# Jukebox_Processing.net
KiCad netlist of a schematic drawn in Altium Designer
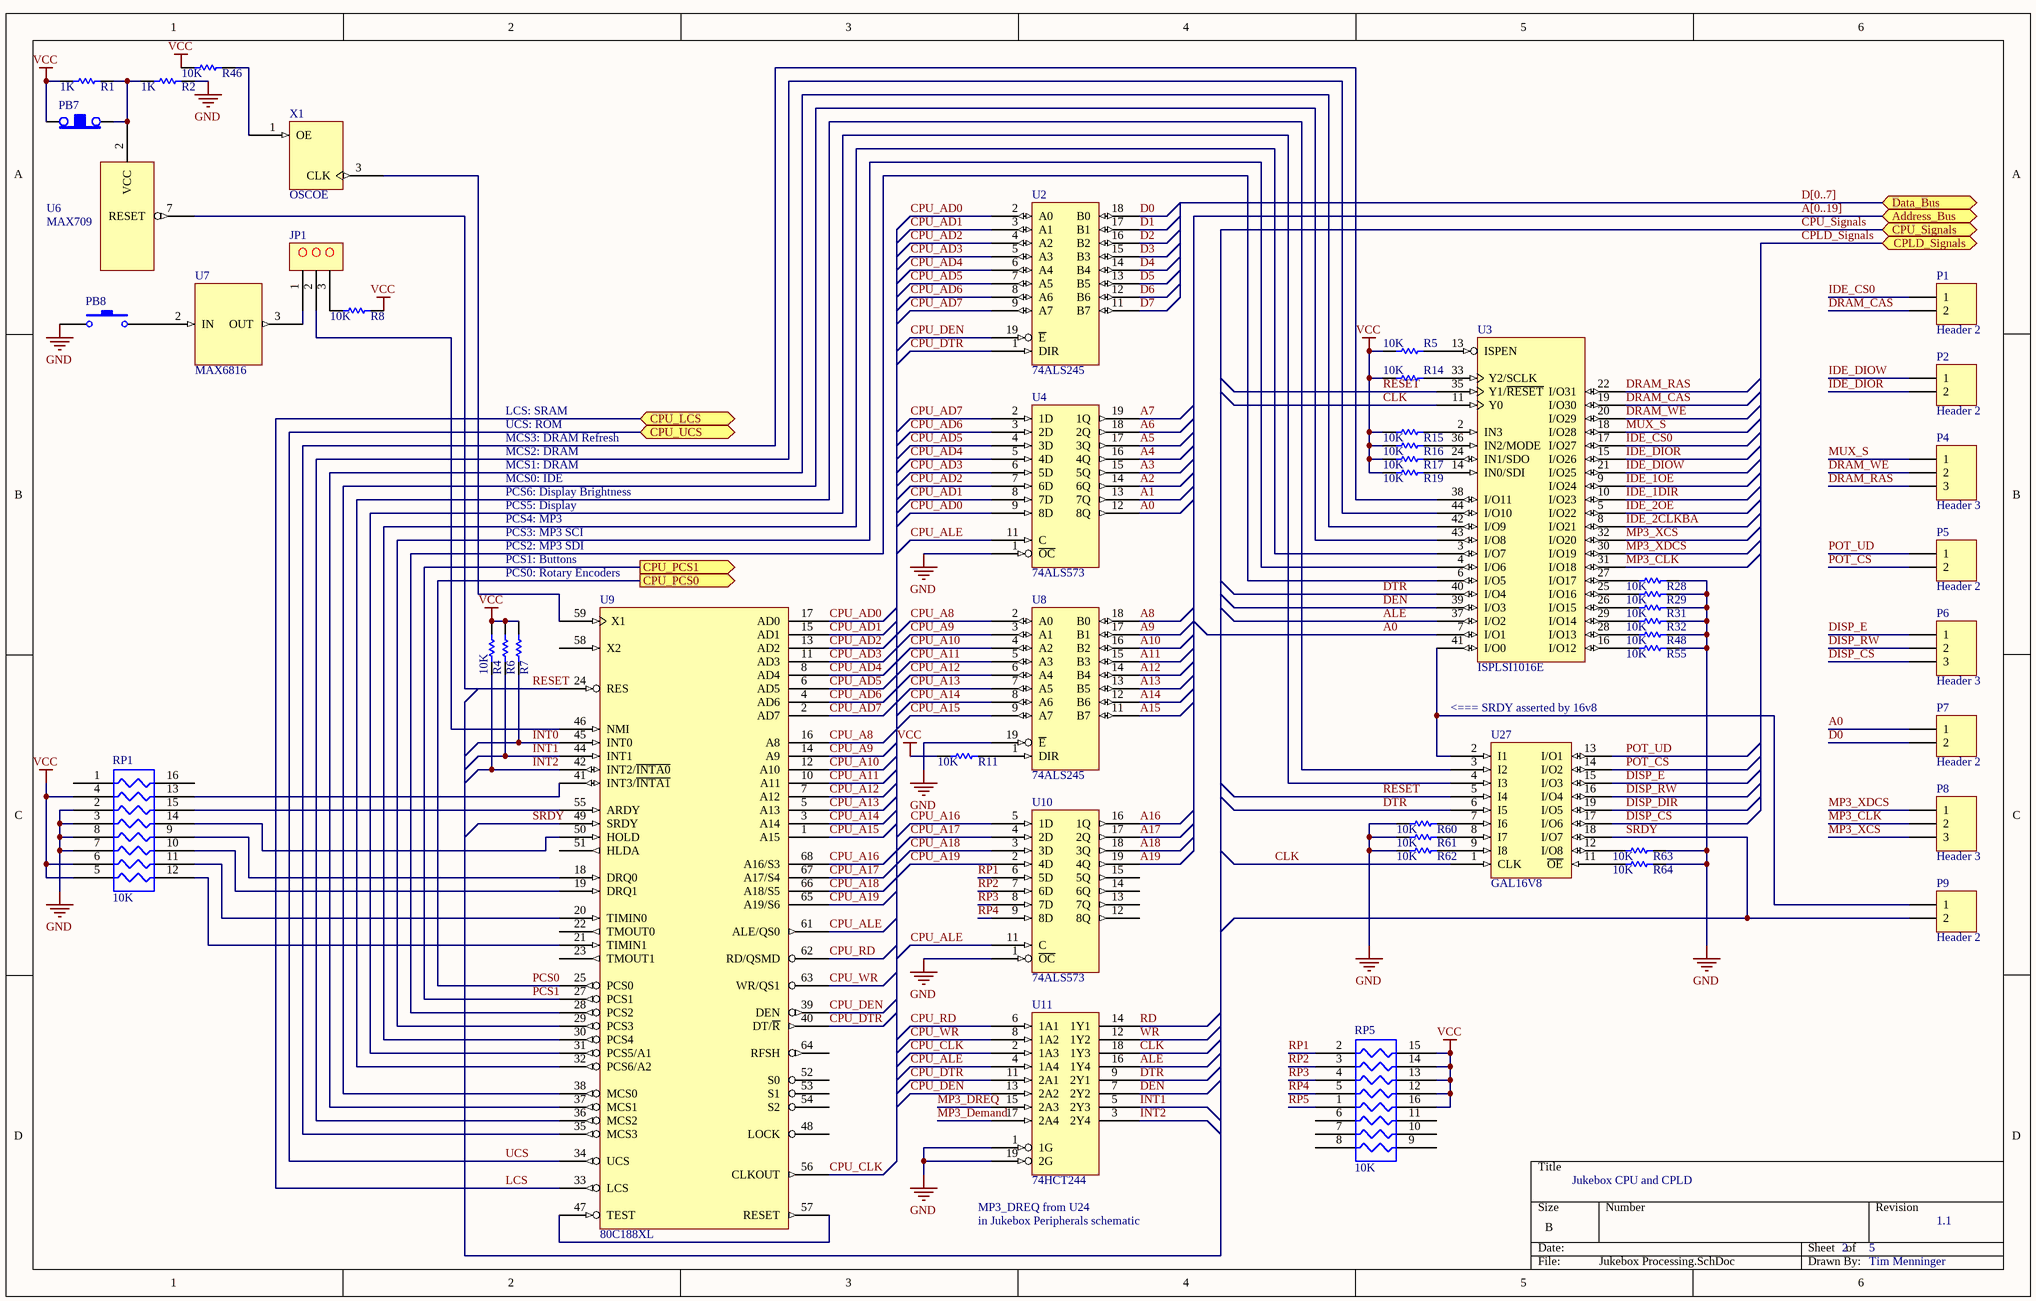
[diagram p0: Jukebox Processing.SchDoc]

(export (version "E")
  (design (tool "Eeschema 10.0.6"))
  (components
    (comp (ref "JP1") (value "3P_JP") (footprint "HDR1X3") (libsource (lib "eecs52_Tim") (part "3P_JP")))
    (comp (ref "P1")
      (value "Header 2")
      (footprint "HDR1X2")
      (description "Header, 2-Pin")
      (fields (field (name "PUBLISHER") "Altium Limited"))
      (libsource (lib "Miscellaneous Connectors") (part "Header 2"))
    )
    (comp (ref "P2")
      (value "Header 2")
      (footprint "HDR1X2")
      (description "Header, 2-Pin")
      (fields (field (name "PUBLISHER") "Altium Limited"))
      (libsource (lib "Miscellaneous Connectors") (part "Header 2"))
    )
    (comp (ref "P4")
      (value "Header 3")
      (footprint "HDR1X3")
      (description "Header, 3-Pin")
      (fields (field (name "PUBLISHER") "Altium Limited"))
      (libsource (lib "Miscellaneous Connectors") (part "Header 3"))
    )
    (comp (ref "P5")
      (value "Header 2")
      (footprint "HDR1X2")
      (description "Header, 2-Pin")
      (fields (field (name "PUBLISHER") "Altium Limited"))
      (libsource (lib "Miscellaneous Connectors") (part "Header 2"))
    )
    (comp (ref "P6")
      (value "Header 3")
      (footprint "HDR1X3")
      (description "Header, 3-Pin")
      (fields (field (name "PUBLISHER") "Altium Limited"))
      (libsource (lib "Miscellaneous Connectors") (part "Header 3"))
    )
    (comp (ref "P7")
      (value "Header 2")
      (footprint "HDR1X2")
      (description "Header, 2-Pin")
      (fields (field (name "PUBLISHER") "Altium Limited"))
      (libsource (lib "Miscellaneous Connectors") (part "Header 2"))
    )
    (comp (ref "P8")
      (value "Header 3")
      (footprint "HDR1X3")
      (description "Header, 3-Pin")
      (fields (field (name "PUBLISHER") "Altium Limited"))
      (libsource (lib "Miscellaneous Connectors") (part "Header 3"))
    )
    (comp (ref "P9")
      (value "Header 2")
      (footprint "HDR1X2")
      (description "Header, 2-Pin")
      (fields (field (name "PUBLISHER") "Altium Limited"))
      (libsource (lib "Miscellaneous Connectors") (part "Header 2"))
    )
    (comp (ref "PB7")
      (value "SWITCH-PBNC")
      (footprint "KSR_PB_NC")
      (description "Normally Closed Pushbutton Switch")
      (libsource (lib "eecs5x") (part "SWITCH-PBNC"))
    )
    (comp (ref "PB8")
      (value "SW-PB")
      (footprint "KSR_PB_NC")
      (description "Switch")
      (fields (field (name "PUBLISHER") "Altium Limited"))
      (libsource (lib "Miscellaneous Devices") (part "SW-PB"))
    )
    (comp (ref "R1")
      (value "1K")
      (footprint "6-0805_L")
      (description "Resistor")
      (fields (field (name "Comment") "Res1") (field (name "PUBLISHER") "Altium Limited"))
      (libsource (lib "Miscellaneous Devices") (part "Res1"))
    )
    (comp (ref "R2")
      (value "1K")
      (footprint "6-0805_L")
      (description "Resistor")
      (fields (field (name "Comment") "Res1") (field (name "PUBLISHER") "Altium Limited"))
      (libsource (lib "Miscellaneous Devices") (part "Res1"))
    )
    (comp (ref "R4")
      (value "10K")
      (footprint "6-0805_L")
      (description "Resistor")
      (fields (field (name "Comment") "Res1") (field (name "PUBLISHER") "Altium Limited"))
      (libsource (lib "Miscellaneous Devices") (part "Res1"))
    )
    (comp (ref "R5")
      (value "10K")
      (footprint "6-0805_L")
      (description "Resistor")
      (fields (field (name "Comment") "Res1") (field (name "PUBLISHER") "Altium Limited"))
      (libsource (lib "Miscellaneous Devices") (part "Res1"))
    )
    (comp (ref "R6")
      (value "Res1")
      (footprint "6-0805_L")
      (description "Resistor")
      (fields (field (name "PUBLISHER") "Altium Limited"))
      (libsource (lib "Miscellaneous Devices") (part "Res1"))
    )
    (comp (ref "R7")
      (value "Res1")
      (footprint "6-0805_L")
      (description "Resistor")
      (fields (field (name "PUBLISHER") "Altium Limited"))
      (libsource (lib "Miscellaneous Devices") (part "Res1"))
    )
    (comp (ref "R8")
      (value "10K")
      (footprint "6-0805_L")
      (description "Resistor")
      (fields (field (name "Comment") "Res1") (field (name "PUBLISHER") "Altium Limited"))
      (libsource (lib "Miscellaneous Devices") (part "Res1"))
    )
    (comp (ref "R11")
      (value "10K")
      (footprint "6-0805_L")
      (description "Resistor")
      (fields (field (name "Comment") "Res1") (field (name "PUBLISHER") "Altium Limited"))
      (libsource (lib "Miscellaneous Devices") (part "Res1"))
    )
    (comp (ref "R14")
      (value "10K")
      (footprint "6-0805_L")
      (description "Resistor")
      (fields (field (name "Comment") "Res1") (field (name "PUBLISHER") "Altium Limited"))
      (libsource (lib "Miscellaneous Devices") (part "Res1"))
    )
    (comp (ref "R15")
      (value "10K")
      (footprint "6-0805_L")
      (description "Resistor")
      (fields (field (name "Comment") "Res1") (field (name "PUBLISHER") "Altium Limited"))
      (libsource (lib "Miscellaneous Devices") (part "Res1"))
    )
    (comp (ref "R16")
      (value "10K")
      (footprint "6-0805_L")
      (description "Resistor")
      (fields (field (name "Comment") "Res1") (field (name "PUBLISHER") "Altium Limited"))
      (libsource (lib "Miscellaneous Devices") (part "Res1"))
    )
    (comp (ref "R17")
      (value "10K")
      (footprint "6-0805_L")
      (description "Resistor")
      (fields (field (name "Comment") "Res1") (field (name "PUBLISHER") "Altium Limited"))
      (libsource (lib "Miscellaneous Devices") (part "Res1"))
    )
    (comp (ref "R19")
      (value "10K")
      (footprint "6-0805_L")
      (description "Resistor")
      (fields (field (name "Comment") "Res1") (field (name "PUBLISHER") "Altium Limited"))
      (libsource (lib "Miscellaneous Devices") (part "Res1"))
    )
    (comp (ref "R28")
      (value "10K")
      (footprint "6-0805_L")
      (description "Resistor")
      (fields (field (name "Comment") "Res1") (field (name "PUBLISHER") "Altium Limited"))
      (libsource (lib "Miscellaneous Devices") (part "Res1"))
    )
    (comp (ref "R29")
      (value "10K")
      (footprint "6-0805_L")
      (description "Resistor")
      (fields (field (name "Comment") "Res1") (field (name "PUBLISHER") "Altium Limited"))
      (libsource (lib "Miscellaneous Devices") (part "Res1"))
    )
    (comp (ref "R31")
      (value "10K")
      (footprint "6-0805_L")
      (description "Resistor")
      (fields (field (name "Comment") "Res1") (field (name "PUBLISHER") "Altium Limited"))
      (libsource (lib "Miscellaneous Devices") (part "Res1"))
    )
    (comp (ref "R32")
      (value "10K")
      (footprint "6-0805_L")
      (description "Resistor")
      (fields (field (name "Comment") "Res1") (field (name "PUBLISHER") "Altium Limited"))
      (libsource (lib "Miscellaneous Devices") (part "Res1"))
    )
    (comp (ref "R46")
      (value "10K")
      (footprint "6-0805_L")
      (description "Resistor")
      (fields (field (name "Comment") "Res1") (field (name "PUBLISHER") "Altium Limited"))
      (libsource (lib "Miscellaneous Devices") (part "Res1"))
    )
    (comp (ref "R48")
      (value "10K")
      (footprint "6-0805_L")
      (description "Resistor")
      (fields (field (name "Comment") "Res1") (field (name "PUBLISHER") "Altium Limited"))
      (libsource (lib "Miscellaneous Devices") (part "Res1"))
    )
    (comp (ref "R55")
      (value "10K")
      (footprint "6-0805_L")
      (description "Resistor")
      (fields (field (name "Comment") "Res1") (field (name "PUBLISHER") "Altium Limited"))
      (libsource (lib "Miscellaneous Devices") (part "Res1"))
    )
    (comp (ref "R60")
      (value "10K")
      (footprint "6-0805_L")
      (description "Resistor")
      (fields (field (name "Comment") "Res1") (field (name "PUBLISHER") "Altium Limited"))
      (libsource (lib "Miscellaneous Devices") (part "Res1"))
    )
    (comp (ref "R61")
      (value "10K")
      (footprint "6-0805_L")
      (description "Resistor")
      (fields (field (name "Comment") "Res1") (field (name "PUBLISHER") "Altium Limited"))
      (libsource (lib "Miscellaneous Devices") (part "Res1"))
    )
    (comp (ref "R62")
      (value "10K")
      (footprint "6-0805_L")
      (description "Resistor")
      (fields (field (name "Comment") "Res1") (field (name "PUBLISHER") "Altium Limited"))
      (libsource (lib "Miscellaneous Devices") (part "Res1"))
    )
    (comp (ref "R63")
      (value "10K")
      (footprint "6-0805_L")
      (description "Resistor")
      (fields (field (name "Comment") "Res1") (field (name "PUBLISHER") "Altium Limited"))
      (libsource (lib "Miscellaneous Devices") (part "Res1"))
    )
    (comp (ref "R64")
      (value "10K")
      (footprint "6-0805_L")
      (description "Resistor")
      (fields (field (name "Comment") "Res1") (field (name "PUBLISHER") "Altium Limited"))
      (libsource (lib "Miscellaneous Devices") (part "Res1"))
    )
    (comp (ref "RP1")
      (value "10K")
      (footprint "SSOP16")
      (description "Resistor Pack - 8 Resistors")
      (libsource (lib "eecs5x") (part "RPACK8"))
    )
    (comp (ref "RP5")
      (value "10K")
      (footprint "SSOP16")
      (description "Resistor Pack - 8 Resistors")
      (libsource (lib "") (part "RPACK8_1"))
    )
    (comp (ref "U2")
      (value "74ALS245")
      (footprint "SSOP20")
      (description "Octal Bus Transceiver")
      (libsource (lib "eecs5x") (part "74ALS245"))
    )
    (comp (ref "U3")
      (value "ISPLSI1016E")
      (footprint "PLCCS44")
      (description "In-System Programmable High Density CPLD")
      (libsource (lib "eecs5x") (part "ISPLSI1016"))
    )
    (comp (ref "U4")
      (value "74ALS573")
      (footprint "SSOP20")
      (description "Octal Transparent Latch")
      (libsource (lib "eecs5x") (part "74ALS573"))
    )
    (comp (ref "U6")
      (value "MAX709")
      (footprint "UMAX8")
      (description "Maxim Power-On Reset")
      (libsource (lib "eecs5x") (part "MAX709"))
    )
    (comp (ref "U7")
      (value "MAX6816")
      (footprint "SOT-143")
      (description "Single Switch Debouncer")
      (libsource (lib "eecs5x") (part "MAX6816"))
    )
    (comp (ref "U8")
      (value "74ALS245")
      (footprint "SSOP20")
      (description "Octal Bus Transceiver")
      (libsource (lib "eecs5x") (part "74ALS245"))
    )
    (comp (ref "U9")
      (value "80C188XL")
      (footprint "PLCCS68I")
      (description "Intel 80188 Microprocessor")
      (libsource (lib "eecs5x") (part "80C188XL"))
    )
    (comp (ref "U10")
      (value "74ALS573")
      (footprint "SSOP20")
      (description "Octal Transparent Latch")
      (libsource (lib "") (part "74ALS573_1"))
    )
    (comp (ref "U11")
      (value "74HCT244")
      (footprint "SSOP20")
      (description "Octal Buffer")
      (libsource (lib "eecs5x") (part "74HCT244"))
    )
    (comp (ref "U27") (value "GAL16V8") (footprint "DIPS20") (libsource (lib "eecs52_Tim") (part "GAL16V8")))
    (comp (ref "X1")
      (value "OSCOE")
      (footprint "DIPS8-4")
      (description "Oscillator with Active High Output Enable")
      (libsource (lib "eecs5x") (part "OSCOE"))
    )
  )
  (nets
    (net (code "3") (name "/A0") (class "Default")
      (node (ref "P7") (pin "1") (pinfunction "1_1") (pintype "passive"))
      (node (ref "U3") (pin "7") (pinfunction "I/O1_7") (pintype "bidirectional"))
      (node (ref "U4") (pin "12") (pinfunction "8Q_12") (pintype "output"))
    )
    (net (code "4") (name "/A1") (class "Default")
      (node (ref "U4") (pin "13") (pinfunction "7Q_13") (pintype "output"))
    )
    (net (code "5") (name "/A2") (class "Default")
      (node (ref "U4") (pin "14") (pinfunction "6Q_14") (pintype "output"))
    )
    (net (code "6") (name "/A3") (class "Default")
      (node (ref "U4") (pin "15") (pinfunction "5Q_15") (pintype "output"))
    )
    (net (code "7") (name "/A4") (class "Default")
      (node (ref "U4") (pin "16") (pinfunction "4Q_16") (pintype "output"))
    )
    (net (code "8") (name "/A5") (class "Default")
      (node (ref "U4") (pin "17") (pinfunction "3Q_17") (pintype "output"))
    )
    (net (code "9") (name "/A6") (class "Default")
      (node (ref "U4") (pin "18") (pinfunction "2Q_18") (pintype "output"))
    )
    (net (code "10") (name "/A7") (class "Default")
      (node (ref "U4") (pin "19") (pinfunction "1Q_19") (pintype "output"))
    )
    (net (code "11") (name "/A8") (class "Default")
      (node (ref "U8") (pin "18") (pinfunction "B0_18") (pintype "bidirectional"))
    )
    (net (code "12") (name "/A9") (class "Default")
      (node (ref "U8") (pin "17") (pinfunction "B1_17") (pintype "bidirectional"))
    )
    (net (code "13") (name "/A10") (class "Default")
      (node (ref "U8") (pin "16") (pinfunction "B2_16") (pintype "bidirectional"))
    )
    (net (code "14") (name "/A11") (class "Default")
      (node (ref "U8") (pin "15") (pinfunction "B3_15") (pintype "bidirectional"))
    )
    (net (code "15") (name "/A12") (class "Default")
      (node (ref "U8") (pin "14") (pinfunction "B4_14") (pintype "bidirectional"))
    )
    (net (code "16") (name "/A13") (class "Default")
      (node (ref "U8") (pin "13") (pinfunction "B5_13") (pintype "bidirectional"))
    )
    (net (code "17") (name "/A14") (class "Default")
      (node (ref "U8") (pin "12") (pinfunction "B6_12") (pintype "bidirectional"))
    )
    (net (code "18") (name "/A15") (class "Default")
      (node (ref "U8") (pin "11") (pinfunction "B7_11") (pintype "bidirectional"))
    )
    (net (code "19") (name "/A16") (class "Default")
      (node (ref "U10") (pin "16") (pinfunction "1Q_16") (pintype "output"))
    )
    (net (code "20") (name "/A17") (class "Default")
      (node (ref "U10") (pin "17") (pinfunction "2Q_17") (pintype "output"))
    )
    (net (code "21") (name "/A18") (class "Default")
      (node (ref "U10") (pin "18") (pinfunction "3Q_18") (pintype "output"))
    )
    (net (code "22") (name "/A19") (class "Default")
      (node (ref "U10") (pin "19") (pinfunction "4Q_19") (pintype "output"))
    )
    (net (code "23") (name "/ALE") (class "Default")
      (node (ref "U11") (pin "16") (pinfunction "1Y4_16") (pintype "tri_state"))
      (node (ref "U3") (pin "37") (pinfunction "I/O2_37") (pintype "bidirectional"))
    )
    (net (code "25") (name "/CLK") (class "Default")
      (node (ref "U11") (pin "18") (pinfunction "1Y3_18") (pintype "tri_state"))
      (node (ref "U27") (pin "1") (pinfunction "CLK_1") (pintype "input"))
      (node (ref "U3") (pin "11") (pinfunction "Y0_11") (pintype "input"))
    )
    (net (code "26") (name "/CPU_A8") (class "Default")
      (node (ref "U8") (pin "2") (pinfunction "A0_2") (pintype "bidirectional"))
      (node (ref "U9") (pin "16") (pinfunction "A8_16") (pintype "tri_state"))
    )
    (net (code "27") (name "/CPU_A9") (class "Default")
      (node (ref "U8") (pin "3") (pinfunction "A1_3") (pintype "bidirectional"))
      (node (ref "U9") (pin "14") (pinfunction "A9_14") (pintype "tri_state"))
    )
    (net (code "28") (name "/CPU_A10") (class "Default")
      (node (ref "U8") (pin "4") (pinfunction "A2_4") (pintype "bidirectional"))
      (node (ref "U9") (pin "12") (pinfunction "A10_12") (pintype "tri_state"))
    )
    (net (code "29") (name "/CPU_A11") (class "Default")
      (node (ref "U8") (pin "5") (pinfunction "A3_5") (pintype "bidirectional"))
      (node (ref "U9") (pin "10") (pinfunction "A11_10") (pintype "tri_state"))
    )
    (net (code "30") (name "/CPU_A12") (class "Default")
      (node (ref "U8") (pin "6") (pinfunction "A4_6") (pintype "bidirectional"))
      (node (ref "U9") (pin "7") (pinfunction "A12_7") (pintype "tri_state"))
    )
    (net (code "31") (name "/CPU_A13") (class "Default")
      (node (ref "U8") (pin "7") (pinfunction "A5_7") (pintype "bidirectional"))
      (node (ref "U9") (pin "5") (pinfunction "A13_5") (pintype "tri_state"))
    )
    (net (code "32") (name "/CPU_A14") (class "Default")
      (node (ref "U8") (pin "8") (pinfunction "A6_8") (pintype "bidirectional"))
      (node (ref "U9") (pin "3") (pinfunction "A14_3") (pintype "tri_state"))
    )
    (net (code "33") (name "/CPU_A15") (class "Default")
      (node (ref "U8") (pin "9") (pinfunction "A7_9") (pintype "bidirectional"))
      (node (ref "U9") (pin "1") (pinfunction "A15_1") (pintype "tri_state"))
    )
    (net (code "34") (name "/CPU_A16") (class "Default")
      (node (ref "U10") (pin "5") (pinfunction "1D_5") (pintype "input"))
      (node (ref "U9") (pin "68") (pinfunction "A16/S3_68") (pintype "tri_state"))
    )
    (net (code "35") (name "/CPU_A17") (class "Default")
      (node (ref "U10") (pin "4") (pinfunction "2D_4") (pintype "input"))
      (node (ref "U9") (pin "67") (pinfunction "A17/S4_67") (pintype "tri_state"))
    )
    (net (code "36") (name "/CPU_A18") (class "Default")
      (node (ref "U10") (pin "3") (pinfunction "3D_3") (pintype "input"))
      (node (ref "U9") (pin "66") (pinfunction "A18/S5_66") (pintype "tri_state"))
    )
    (net (code "37") (name "/CPU_A19") (class "Default")
      (node (ref "U10") (pin "2") (pinfunction "4D_2") (pintype "input"))
      (node (ref "U9") (pin "65") (pinfunction "A19/S6_65") (pintype "tri_state"))
    )
    (net (code "38") (name "/CPU_AD0") (class "Default")
      (node (ref "U2") (pin "2") (pinfunction "A0_2") (pintype "bidirectional"))
      (node (ref "U4") (pin "9") (pinfunction "8D_9") (pintype "input"))
      (node (ref "U9") (pin "17") (pinfunction "AD0_17") (pintype "tri_state"))
    )
    (net (code "39") (name "/CPU_AD1") (class "Default")
      (node (ref "U2") (pin "3") (pinfunction "A1_3") (pintype "bidirectional"))
      (node (ref "U4") (pin "8") (pinfunction "7D_8") (pintype "input"))
      (node (ref "U9") (pin "15") (pinfunction "AD1_15") (pintype "tri_state"))
    )
    (net (code "40") (name "/CPU_AD2") (class "Default")
      (node (ref "U2") (pin "4") (pinfunction "A2_4") (pintype "bidirectional"))
      (node (ref "U4") (pin "7") (pinfunction "6D_7") (pintype "input"))
      (node (ref "U9") (pin "13") (pinfunction "AD2_13") (pintype "tri_state"))
    )
    (net (code "41") (name "/CPU_AD3") (class "Default")
      (node (ref "U2") (pin "5") (pinfunction "A3_5") (pintype "bidirectional"))
      (node (ref "U4") (pin "6") (pinfunction "5D_6") (pintype "input"))
      (node (ref "U9") (pin "11") (pinfunction "AD3_11") (pintype "tri_state"))
    )
    (net (code "42") (name "/CPU_AD4") (class "Default")
      (node (ref "U2") (pin "6") (pinfunction "A4_6") (pintype "bidirectional"))
      (node (ref "U4") (pin "5") (pinfunction "4D_5") (pintype "input"))
      (node (ref "U9") (pin "8") (pinfunction "AD4_8") (pintype "tri_state"))
    )
    (net (code "43") (name "/CPU_AD5") (class "Default")
      (node (ref "U2") (pin "7") (pinfunction "A5_7") (pintype "bidirectional"))
      (node (ref "U4") (pin "4") (pinfunction "3D_4") (pintype "input"))
      (node (ref "U9") (pin "6") (pinfunction "AD5_6") (pintype "tri_state"))
    )
    (net (code "44") (name "/CPU_AD6") (class "Default")
      (node (ref "U2") (pin "8") (pinfunction "A6_8") (pintype "bidirectional"))
      (node (ref "U4") (pin "3") (pinfunction "2D_3") (pintype "input"))
      (node (ref "U9") (pin "4") (pinfunction "AD6_4") (pintype "tri_state"))
    )
    (net (code "45") (name "/CPU_AD7") (class "Default")
      (node (ref "U2") (pin "9") (pinfunction "A7_9") (pintype "bidirectional"))
      (node (ref "U4") (pin "2") (pinfunction "1D_2") (pintype "input"))
      (node (ref "U9") (pin "2") (pinfunction "AD7_2") (pintype "tri_state"))
    )
    (net (code "46") (name "/CPU_ALE") (class "Default")
      (node (ref "U10") (pin "11") (pinfunction "C_11") (pintype "input"))
      (node (ref "U11") (pin "4") (pinfunction "1A4_4") (pintype "input"))
      (node (ref "U4") (pin "11") (pinfunction "C_11") (pintype "input"))
      (node (ref "U9") (pin "61") (pinfunction "ALE/QS0_61") (pintype "output"))
    )
    (net (code "47") (name "/CPU_CLK") (class "Default")
      (node (ref "U11") (pin "2") (pinfunction "1A3_2") (pintype "input"))
      (node (ref "U9") (pin "56") (pinfunction "CLKOUT_56") (pintype "output"))
    )
    (net (code "48") (name "/CPU_DEN") (class "Default")
      (node (ref "U11") (pin "13") (pinfunction "2A2_13") (pintype "input"))
      (node (ref "U2") (pin "19") (pinfunction "~{E}_19") (pintype "input"))
      (node (ref "U9") (pin "39") (pinfunction "DEN_39") (pintype "output"))
    )
    (net (code "49") (name "/CPU_DTR") (class "Default")
      (node (ref "U11") (pin "11") (pinfunction "2A1_11") (pintype "input"))
      (node (ref "U2") (pin "1") (pinfunction "DIR_1") (pintype "input"))
      (node (ref "U9") (pin "40") (pinfunction "DT/~{R}_40") (pintype "output"))
    )
    (net (code "50") (name "/CPU_RD") (class "Default")
      (node (ref "U11") (pin "6") (pinfunction "1A1_6") (pintype "input"))
      (node (ref "U9") (pin "62") (pinfunction "RD/QSMD_62") (pintype "tri_state"))
    )
    (net (code "51") (name "/CPU_WR") (class "Default")
      (node (ref "U11") (pin "8") (pinfunction "1A2_8") (pintype "input"))
      (node (ref "U9") (pin "63") (pinfunction "WR/QS1_63") (pintype "tri_state"))
    )
    (net (code "52") (name "/D0") (class "Default")
      (node (ref "P7") (pin "2") (pinfunction "2_2") (pintype "passive"))
      (node (ref "U2") (pin "18") (pinfunction "B0_18") (pintype "bidirectional"))
    )
    (net (code "53") (name "/D1") (class "Default")
      (node (ref "U2") (pin "17") (pinfunction "B1_17") (pintype "bidirectional"))
    )
    (net (code "54") (name "/D2") (class "Default")
      (node (ref "U2") (pin "16") (pinfunction "B2_16") (pintype "bidirectional"))
    )
    (net (code "55") (name "/D3") (class "Default")
      (node (ref "U2") (pin "15") (pinfunction "B3_15") (pintype "bidirectional"))
    )
    (net (code "56") (name "/D4") (class "Default")
      (node (ref "U2") (pin "14") (pinfunction "B4_14") (pintype "bidirectional"))
    )
    (net (code "57") (name "/D5") (class "Default")
      (node (ref "U2") (pin "13") (pinfunction "B5_13") (pintype "bidirectional"))
    )
    (net (code "58") (name "/D6") (class "Default")
      (node (ref "U2") (pin "12") (pinfunction "B6_12") (pintype "bidirectional"))
    )
    (net (code "59") (name "/D7") (class "Default")
      (node (ref "U2") (pin "11") (pinfunction "B7_11") (pintype "bidirectional"))
    )
    (net (code "60") (name "/DEN") (class "Default")
      (node (ref "U11") (pin "7") (pinfunction "2Y2_7") (pintype "tri_state"))
      (node (ref "U3") (pin "39") (pinfunction "I/O3_39") (pintype "bidirectional"))
    )
    (net (code "61") (name "/DISP_CS") (class "Default")
      (node (ref "P6") (pin "3") (pinfunction "3_3") (pintype "passive"))
      (node (ref "U27") (pin "17") (pinfunction "I/O6_17") (pintype "bidirectional"))
    )
    (net (code "62") (name "/DISP_DIR") (class "Default")
      (node (ref "U27") (pin "19") (pinfunction "I/O5_19") (pintype "bidirectional"))
    )
    (net (code "63") (name "/DISP_E") (class "Default")
      (node (ref "P6") (pin "1") (pinfunction "1_1") (pintype "passive"))
      (node (ref "U27") (pin "15") (pinfunction "I/O3_15") (pintype "bidirectional"))
    )
    (net (code "64") (name "/DISP_RW") (class "Default")
      (node (ref "P6") (pin "2") (pinfunction "2_2") (pintype "passive"))
      (node (ref "U27") (pin "16") (pinfunction "I/O4_16") (pintype "bidirectional"))
    )
    (net (code "65") (name "/DRAM_CAS") (class "Default")
      (node (ref "P1") (pin "2") (pinfunction "2_2") (pintype "passive"))
      (node (ref "U3") (pin "19") (pinfunction "I/O30_19") (pintype "bidirectional"))
    )
    (net (code "66") (name "/DRAM_RAS") (class "Default")
      (node (ref "P4") (pin "3") (pinfunction "3_3") (pintype "passive"))
      (node (ref "U3") (pin "22") (pinfunction "I/O31_22") (pintype "bidirectional"))
    )
    (net (code "67") (name "/DRAM_WE") (class "Default")
      (node (ref "P4") (pin "2") (pinfunction "2_2") (pintype "passive"))
      (node (ref "U3") (pin "20") (pinfunction "I/O29_20") (pintype "bidirectional"))
    )
    (net (code "68") (name "/DTR") (class "Default")
      (node (ref "U11") (pin "9") (pinfunction "2Y1_9") (pintype "tri_state"))
      (node (ref "U27") (pin "6") (pinfunction "I5_6") (pintype "input"))
      (node (ref "U3") (pin "40") (pinfunction "I/O4_40") (pintype "bidirectional"))
    )
    (net (code "70") (name "/IDE_1DIR") (class "Default")
      (node (ref "U3") (pin "10") (pinfunction "I/O23_10") (pintype "bidirectional"))
    )
    (net (code "71") (name "/IDE_1OE") (class "Default")
      (node (ref "U3") (pin "9") (pinfunction "I/O24_9") (pintype "bidirectional"))
    )
    (net (code "72") (name "/IDE_2CLKBA") (class "Default")
      (node (ref "U3") (pin "8") (pinfunction "I/O21_8") (pintype "bidirectional"))
    )
    (net (code "73") (name "/IDE_2OE") (class "Default")
      (node (ref "U3") (pin "5") (pinfunction "I/O22_5") (pintype "bidirectional"))
    )
    (net (code "74") (name "/IDE_CS0") (class "Default")
      (node (ref "P1") (pin "1") (pinfunction "1_1") (pintype "passive"))
      (node (ref "U3") (pin "17") (pinfunction "I/O27_17") (pintype "bidirectional"))
    )
    (net (code "75") (name "/IDE_DIOR") (class "Default")
      (node (ref "P2") (pin "2") (pinfunction "2_2") (pintype "passive"))
      (node (ref "U3") (pin "15") (pinfunction "I/O26_15") (pintype "bidirectional"))
    )
    (net (code "76") (name "/IDE_DIOW") (class "Default")
      (node (ref "P2") (pin "1") (pinfunction "1_1") (pintype "passive"))
      (node (ref "U3") (pin "21") (pinfunction "I/O25_21") (pintype "bidirectional"))
    )
    (net (code "77") (name "/INT0") (class "Default")
      (node (ref "R7") (pin "1") (pinfunction "1_1") (pintype "passive"))
      (node (ref "U9") (pin "45") (pinfunction "INT0_45") (pintype "input"))
    )
    (net (code "78") (name "/INT1") (class "Default")
      (node (ref "R6") (pin "1") (pinfunction "1_1") (pintype "passive"))
      (node (ref "U11") (pin "5") (pinfunction "2Y3_5") (pintype "tri_state"))
      (node (ref "U9") (pin "44") (pinfunction "INT1_44") (pintype "input"))
    )
    (net (code "79") (name "/INT2") (class "Default")
      (node (ref "R4") (pin "1") (pinfunction "1_1") (pintype "passive"))
      (node (ref "U11") (pin "3") (pinfunction "2Y4_3") (pintype "tri_state"))
      (node (ref "U9") (pin "42") (pinfunction "INT2/~{INTA0}_42") (pintype "bidirectional"))
    )
    (net (code "80") (name "/LCS") (class "Default")
      (node (ref "U9") (pin "33") (pinfunction "LCS_33") (pintype "output"))
    )
    (net (code "81") (name "/MP3_CLK") (class "Default")
      (node (ref "P8") (pin "2") (pinfunction "2_2") (pintype "passive"))
      (node (ref "U3") (pin "31") (pinfunction "I/O18_31") (pintype "bidirectional"))
    )
    (net (code "82") (name "/MP3_DREQ") (class "Default")
      (node (ref "U11") (pin "15") (pinfunction "2A3_15") (pintype "input"))
    )
    (net (code "83") (name "/MP3_Demand") (class "Default")
      (node (ref "U11") (pin "17") (pinfunction "2A4_17") (pintype "input"))
    )
    (net (code "84") (name "/MP3_XCS") (class "Default")
      (node (ref "P8") (pin "3") (pinfunction "3_3") (pintype "passive"))
      (node (ref "U3") (pin "32") (pinfunction "I/O20_32") (pintype "bidirectional"))
    )
    (net (code "85") (name "/MP3_XDCS") (class "Default")
      (node (ref "P8") (pin "1") (pinfunction "1_1") (pintype "passive"))
      (node (ref "U3") (pin "30") (pinfunction "I/O19_30") (pintype "bidirectional"))
    )
    (net (code "86") (name "/MUX_S") (class "Default")
      (node (ref "P4") (pin "1") (pinfunction "1_1") (pintype "passive"))
      (node (ref "U3") (pin "18") (pinfunction "I/O28_18") (pintype "bidirectional"))
    )
    (net (code "87") (name "/PCS0") (class "Default")
      (node (ref "U9") (pin "25") (pinfunction "PCS0_25") (pintype "output"))
    )
    (net (code "88") (name "/PCS1") (class "Default")
      (node (ref "U9") (pin "27") (pinfunction "PCS1_27") (pintype "output"))
    )
    (net (code "89") (name "/POT_CS") (class "Default")
      (node (ref "P5") (pin "2") (pinfunction "2_2") (pintype "passive"))
      (node (ref "U27") (pin "14") (pinfunction "I/O2_14") (pintype "bidirectional"))
    )
    (net (code "90") (name "/POT_UD") (class "Default")
      (node (ref "P5") (pin "1") (pinfunction "1_1") (pintype "passive"))
      (node (ref "U27") (pin "13") (pinfunction "I/O1_13") (pintype "bidirectional"))
    )
    (net (code "91") (name "/RD") (class "Default")
      (node (ref "U11") (pin "14") (pinfunction "1Y1_14") (pintype "tri_state"))
    )
    (net (code "92") (name "/RESET") (class "Default")
      (node (ref "U27") (pin "5") (pinfunction "I4_5") (pintype "input"))
      (node (ref "U3") (pin "35") (pinfunction "Y1/~{RESET}_35") (pintype "input"))
      (node (ref "U6") (pin "7") (pinfunction "RESET_7") (pintype "output"))
      (node (ref "U9") (pin "24") (pinfunction "RES_24") (pintype "input"))
    )
    (net (code "93") (name "/RP1") (class "Default")
      (node (ref "RP5") (pin "2") (pintype "passive"))
      (node (ref "U10") (pin "6") (pinfunction "5D_6") (pintype "input"))
    )
    (net (code "94") (name "/RP2") (class "Default")
      (node (ref "RP5") (pin "3") (pintype "passive"))
      (node (ref "U10") (pin "7") (pinfunction "6D_7") (pintype "input"))
    )
    (net (code "95") (name "/RP3") (class "Default")
      (node (ref "RP5") (pin "4") (pintype "passive"))
      (node (ref "U10") (pin "8") (pinfunction "7D_8") (pintype "input"))
    )
    (net (code "96") (name "/RP4") (class "Default")
      (node (ref "RP5") (pin "5") (pintype "passive"))
      (node (ref "U10") (pin "9") (pinfunction "8D_9") (pintype "input"))
    )
    (net (code "97") (name "/RP5") (class "Default") (node (ref "RP5") (pin "1") (pintype "passive")))
    (net (code "98") (name "/SRDY") (class "Default")
      (node (ref "P9") (pin "2") (pinfunction "2_2") (pintype "passive"))
      (node (ref "U27") (pin "18") (pinfunction "I/O7_18") (pintype "bidirectional"))
      (node (ref "U9") (pin "49") (pinfunction "SRDY_49") (pintype "input"))
    )
    (net (code "99") (name "/UCS") (class "Default")
      (node (ref "U9") (pin "34") (pinfunction "UCS_34") (pintype "output"))
    )
    (net (code "100") (name "/WR") (class "Default")
      (node (ref "U11") (pin "12") (pinfunction "1Y2_12") (pintype "tri_state"))
    )
    (net (code "103") (name "GND") (class "Default")
      (node (ref "PB8") (pin "1") (pinfunction "1_1") (pintype "passive"))
      (node (ref "R2") (pin "2") (pinfunction "2_2") (pintype "passive"))
      (node (ref "R28") (pin "2") (pinfunction "2_2") (pintype "passive"))
      (node (ref "R29") (pin "2") (pinfunction "2_2") (pintype "passive"))
      (node (ref "R31") (pin "2") (pinfunction "2_2") (pintype "passive"))
      (node (ref "R32") (pin "2") (pinfunction "2_2") (pintype "passive"))
      (node (ref "R48") (pin "2") (pinfunction "2_2") (pintype "passive"))
      (node (ref "R55") (pin "2") (pinfunction "2_2") (pintype "passive"))
      (node (ref "R60") (pin "1") (pinfunction "1_1") (pintype "passive"))
      (node (ref "R61") (pin "1") (pinfunction "1_1") (pintype "passive"))
      (node (ref "R62") (pin "1") (pinfunction "1_1") (pintype "passive"))
      (node (ref "R63") (pin "2") (pinfunction "2_2") (pintype "passive"))
      (node (ref "R64") (pin "2") (pinfunction "2_2") (pintype "passive"))
      (node (ref "RP1") (pin "2") (pintype "passive"))
      (node (ref "RP1") (pin "3") (pintype "passive"))
      (node (ref "RP1") (pin "7") (pintype "passive"))
      (node (ref "RP1") (pin "8") (pintype "passive"))
      (node (ref "U10") (pin "1") (pinfunction "~{OC}_1") (pintype "input"))
      (node (ref "U10") (pin "10") (pinfunction "GND_10") (pintype "power_in"))
      (node (ref "U11") (pin "1") (pinfunction "1G_1") (pintype "input"))
      (node (ref "U11") (pin "10") (pinfunction "GND_10") (pintype "power_in"))
      (node (ref "U11") (pin "19") (pinfunction "2G_19") (pintype "input"))
      (node (ref "U2") (pin "10") (pinfunction "GND_10") (pintype "power_in"))
      (node (ref "U27") (pin "10") (pinfunction "GND_10") (pintype "power_in"))
      (node (ref "U3") (pin "1") (pinfunction "GND_1") (pintype "power_in"))
      (node (ref "U3") (pin "23") (pinfunction "GND_23") (pintype "power_in"))
      (node (ref "U4") (pin "1") (pinfunction "~{OC}_1") (pintype "input"))
      (node (ref "U4") (pin "10") (pinfunction "GND_10") (pintype "power_in"))
      (node (ref "U6") (pin "3") (pinfunction "GND_3") (pintype "power_in"))
      (node (ref "U7") (pin "1") (pinfunction "GND_1") (pintype "power_in"))
      (node (ref "U8") (pin "10") (pinfunction "GND_10") (pintype "power_in"))
      (node (ref "U8") (pin "19") (pinfunction "~{E}_19") (pintype "input"))
      (node (ref "U9") (pin "26") (pinfunction "GND_26") (pintype "power_in"))
      (node (ref "U9") (pin "60") (pinfunction "GND_60") (pintype "power_in"))
      (node (ref "X1") (pin "2") (pinfunction "GND_2") (pintype "power_in"))
    )
    (net (code "104") (name "Net-(JP1-Pad3)") (class "Default")
      (node (ref "JP1") (pin "3") (pintype "passive"))
      (node (ref "R8") (pin "1") (pinfunction "1_1") (pintype "passive"))
    )
    (net (code "105") (name "Net-(U3-IN0{slash}SDI)") (class "Default")
      (node (ref "R19") (pin "2") (pinfunction "2_2") (pintype "passive"))
      (node (ref "U3") (pin "14") (pinfunction "IN0/SDI_14") (pintype "input"))
    )
    (net (code "106") (name "Net-(U3-IN1{slash}SDO)") (class "Default")
      (node (ref "R17") (pin "2") (pinfunction "2_2") (pintype "passive"))
      (node (ref "U3") (pin "24") (pinfunction "IN1/SDO_24") (pintype "bidirectional"))
    )
    (net (code "107") (name "Net-(U3-IN2{slash}MODE)") (class "Default")
      (node (ref "R16") (pin "2") (pinfunction "2_2") (pintype "passive"))
      (node (ref "U3") (pin "36") (pinfunction "IN2/MODE_36") (pintype "input"))
    )
    (net (code "108") (name "Net-(U3-IN3)") (class "Default")
      (node (ref "R15") (pin "2") (pinfunction "2_2") (pintype "passive"))
      (node (ref "U3") (pin "2") (pinfunction "IN3_2") (pintype "input"))
    )
    (net (code "109") (name "Net-(U3-ISPEN)") (class "Default")
      (node (ref "R5") (pin "2") (pinfunction "2_2") (pintype "passive"))
      (node (ref "U3") (pin "13") (pinfunction "ISPEN_13") (pintype "input"))
    )
    (net (code "110") (name "Net-(U3-I{slash}O5)") (class "Default")
      (node (ref "U3") (pin "6") (pinfunction "I/O5_6") (pintype "bidirectional"))
      (node (ref "U9") (pin "28") (pinfunction "PCS2_28") (pintype "output"))
    )
    (net (code "111") (name "Net-(U3-I{slash}O6)") (class "Default")
      (node (ref "U3") (pin "4") (pinfunction "I/O6_4") (pintype "bidirectional"))
      (node (ref "U9") (pin "29") (pinfunction "PCS3_29") (pintype "output"))
    )
    (net (code "112") (name "Net-(U3-I{slash}O7)") (class "Default")
      (node (ref "U3") (pin "3") (pinfunction "I/O7_3") (pintype "bidirectional"))
      (node (ref "U9") (pin "30") (pinfunction "PCS4_30") (pintype "output"))
    )
    (net (code "113") (name "Net-(U3-I{slash}O8)") (class "Default")
      (node (ref "U3") (pin "43") (pinfunction "I/O8_43") (pintype "bidirectional"))
      (node (ref "U9") (pin "38") (pinfunction "MCS0_38") (pintype "output"))
    )
    (net (code "114") (name "Net-(U3-I{slash}O9)") (class "Default")
      (node (ref "U3") (pin "42") (pinfunction "I/O9_42") (pintype "bidirectional"))
      (node (ref "U9") (pin "37") (pinfunction "MCS1_37") (pintype "output"))
    )
    (net (code "115") (name "Net-(U3-I{slash}O10)") (class "Default")
      (node (ref "U3") (pin "44") (pinfunction "I/O10_44") (pintype "bidirectional"))
      (node (ref "U9") (pin "36") (pinfunction "MCS2_36") (pintype "output"))
    )
    (net (code "116") (name "Net-(U3-I{slash}O11)") (class "Default")
      (node (ref "U3") (pin "38") (pinfunction "I/O11_38") (pintype "bidirectional"))
      (node (ref "U9") (pin "35") (pinfunction "MCS3_35") (pintype "output"))
    )
    (net (code "117") (name "Net-(U3-I{slash}O12)") (class "Default")
      (node (ref "R55") (pin "1") (pinfunction "1_1") (pintype "passive"))
      (node (ref "U3") (pin "16") (pinfunction "I/O12_16") (pintype "bidirectional"))
    )
    (net (code "118") (name "Net-(U3-I{slash}O13)") (class "Default")
      (node (ref "R48") (pin "1") (pinfunction "1_1") (pintype "passive"))
      (node (ref "U3") (pin "28") (pinfunction "I/O13_28") (pintype "bidirectional"))
    )
    (net (code "119") (name "Net-(U3-I{slash}O14)") (class "Default")
      (node (ref "R32") (pin "1") (pinfunction "1_1") (pintype "passive"))
      (node (ref "U3") (pin "29") (pinfunction "I/O14_29") (pintype "bidirectional"))
    )
    (net (code "120") (name "Net-(U3-I{slash}O15)") (class "Default")
      (node (ref "R31") (pin "1") (pinfunction "1_1") (pintype "passive"))
      (node (ref "U3") (pin "26") (pinfunction "I/O15_26") (pintype "bidirectional"))
    )
    (net (code "121") (name "Net-(U3-I{slash}O16)") (class "Default")
      (node (ref "R29") (pin "1") (pinfunction "1_1") (pintype "passive"))
      (node (ref "U3") (pin "25") (pinfunction "I/O16_25") (pintype "bidirectional"))
    )
    (net (code "122") (name "Net-(U3-I{slash}O17)") (class "Default")
      (node (ref "R28") (pin "1") (pinfunction "1_1") (pintype "passive"))
      (node (ref "U3") (pin "27") (pinfunction "I/O17_27") (pintype "bidirectional"))
    )
    (net (code "123") (name "Net-(U3-Y2{slash}SCLK)") (class "Default")
      (node (ref "R14") (pin "2") (pinfunction "2_2") (pintype "passive"))
      (node (ref "U3") (pin "33") (pinfunction "Y2/SCLK_33") (pintype "input"))
    )
    (net (code "124") (name "Net-(U6-VCC)") (class "Default")
      (node (ref "PB7") (pin "2") (pintype "passive"))
      (node (ref "R1") (pin "2") (pinfunction "2_2") (pintype "passive"))
      (node (ref "R2") (pin "1") (pinfunction "1_1") (pintype "passive"))
      (node (ref "U6") (pin "2") (pinfunction "VCC_2") (pintype "power_in"))
    )
    (net (code "125") (name "Net-(U7-IN)") (class "Default")
      (node (ref "PB8") (pin "2") (pinfunction "2_2") (pintype "passive"))
      (node (ref "U7") (pin "2") (pinfunction "IN_2") (pintype "input"))
    )
    (net (code "126") (name "Net-(U7-OUT)") (class "Default")
      (node (ref "JP1") (pin "1") (pintype "passive"))
      (node (ref "U7") (pin "3") (pinfunction "OUT_3") (pintype "output"))
    )
    (net (code "127") (name "Net-(U8-DIR)") (class "Default")
      (node (ref "R11") (pin "2") (pinfunction "2_2") (pintype "passive"))
      (node (ref "U8") (pin "1") (pinfunction "DIR_1") (pintype "input"))
    )
    (net (code "128") (name "Net-(U9-ARDY)") (class "Default")
      (node (ref "RP1") (pin "15") (pintype "passive"))
      (node (ref "U9") (pin "55") (pinfunction "ARDY_55") (pintype "input"))
    )
    (net (code "129") (name "Net-(U9-DRQ0)") (class "Default")
      (node (ref "RP1") (pin "9") (pintype "passive"))
      (node (ref "U9") (pin "18") (pinfunction "DRQ0_18") (pintype "input"))
    )
    (net (code "130") (name "Net-(U9-DRQ1)") (class "Default")
      (node (ref "RP1") (pin "10") (pintype "passive"))
      (node (ref "U9") (pin "19") (pinfunction "DRQ1_19") (pintype "input"))
    )
    (net (code "131") (name "Net-(U9-HOLD)") (class "Default")
      (node (ref "RP1") (pin "14") (pintype "passive"))
      (node (ref "U9") (pin "50") (pinfunction "HOLD_50") (pintype "input"))
    )
    (net (code "132") (name "Net-(U9-INT3{slash}~{INTA1})") (class "Default")
      (node (ref "RP1") (pin "13") (pintype "passive"))
      (node (ref "U9") (pin "41") (pinfunction "INT3/~{INTA1}_41") (pintype "bidirectional"))
    )
    (net (code "133") (name "Net-(U9-NMI)") (class "Default")
      (node (ref "JP1") (pin "2") (pintype "passive"))
      (node (ref "U9") (pin "46") (pinfunction "NMI_46") (pintype "input"))
    )
    (net (code "134") (name "Net-(U9-RESET)") (class "Default")
      (node (ref "U9") (pin "47") (pinfunction "TEST_47") (pintype "input"))
      (node (ref "U9") (pin "57") (pinfunction "RESET_57") (pintype "output"))
    )
    (net (code "135") (name "Net-(U9-TIMIN0)") (class "Default")
      (node (ref "RP1") (pin "11") (pintype "passive"))
      (node (ref "U9") (pin "20") (pinfunction "TIMIN0_20") (pintype "input"))
    )
    (net (code "136") (name "Net-(U9-TIMIN1)") (class "Default")
      (node (ref "RP1") (pin "12") (pintype "passive"))
      (node (ref "U9") (pin "21") (pinfunction "TIMIN1_21") (pintype "input"))
    )
    (net (code "137") (name "Net-(U9-X1)") (class "Default")
      (node (ref "U9") (pin "59") (pinfunction "X1_59") (pintype "input"))
      (node (ref "X1") (pin "3") (pinfunction "CLK_3") (pintype "output"))
    )
    (net (code "138") (name "Net-(U27-I1)") (class "Default")
      (node (ref "P9") (pin "1") (pinfunction "1_1") (pintype "passive"))
      (node (ref "U27") (pin "2") (pinfunction "I1_2") (pintype "input"))
      (node (ref "U3") (pin "41") (pinfunction "I/O0_41") (pintype "bidirectional"))
    )
    (net (code "139") (name "Net-(U27-I2)") (class "Default")
      (node (ref "U27") (pin "3") (pinfunction "I2_3") (pintype "input"))
      (node (ref "U9") (pin "32") (pinfunction "PCS6/A2_32") (pintype "output"))
    )
    (net (code "140") (name "Net-(U27-I3)") (class "Default")
      (node (ref "U27") (pin "4") (pinfunction "I3_4") (pintype "input"))
      (node (ref "U9") (pin "31") (pinfunction "PCS5/A1_31") (pintype "output"))
    )
    (net (code "141") (name "Net-(U27-I6)") (class "Default")
      (node (ref "R60") (pin "2") (pinfunction "2_2") (pintype "passive"))
      (node (ref "U27") (pin "7") (pinfunction "I6_7") (pintype "input"))
    )
    (net (code "142") (name "Net-(U27-I7)") (class "Default")
      (node (ref "R61") (pin "2") (pinfunction "2_2") (pintype "passive"))
      (node (ref "U27") (pin "8") (pinfunction "I7_8") (pintype "input"))
    )
    (net (code "143") (name "Net-(U27-I8)") (class "Default")
      (node (ref "R62") (pin "2") (pinfunction "2_2") (pintype "passive"))
      (node (ref "U27") (pin "9") (pinfunction "I8_9") (pintype "input"))
    )
    (net (code "144") (name "Net-(U27-I{slash}O8)") (class "Default")
      (node (ref "R63") (pin "1") (pinfunction "1_1") (pintype "passive"))
      (node (ref "U27") (pin "12") (pinfunction "I/O8_12") (pintype "bidirectional"))
    )
    (net (code "145") (name "Net-(U27-~{OE})") (class "Default")
      (node (ref "R64") (pin "1") (pinfunction "1_1") (pintype "passive"))
      (node (ref "U27") (pin "11") (pinfunction "~{OE}_11") (pintype "input"))
    )
    (net (code "146") (name "Net-(X1-OE)") (class "Default")
      (node (ref "R46") (pin "2") (pinfunction "2_2") (pintype "passive"))
      (node (ref "X1") (pin "1") (pinfunction "OE_1") (pintype "input"))
    )
    (net (code "147") (name "VCC") (class "Default")
      (node (ref "PB7") (pin "1") (pintype "passive"))
      (node (ref "R1") (pin "1") (pinfunction "1_1") (pintype "passive"))
      (node (ref "R11") (pin "1") (pinfunction "1_1") (pintype "passive"))
      (node (ref "R14") (pin "1") (pinfunction "1_1") (pintype "passive"))
      (node (ref "R15") (pin "1") (pinfunction "1_1") (pintype "passive"))
      (node (ref "R16") (pin "1") (pinfunction "1_1") (pintype "passive"))
      (node (ref "R17") (pin "1") (pinfunction "1_1") (pintype "passive"))
      (node (ref "R19") (pin "1") (pinfunction "1_1") (pintype "passive"))
      (node (ref "R4") (pin "2") (pinfunction "2_2") (pintype "passive"))
      (node (ref "R46") (pin "1") (pinfunction "1_1") (pintype "passive"))
      (node (ref "R5") (pin "1") (pinfunction "1_1") (pintype "passive"))
      (node (ref "R6") (pin "2") (pinfunction "2_2") (pintype "passive"))
      (node (ref "R7") (pin "2") (pinfunction "2_2") (pintype "passive"))
      (node (ref "R8") (pin "2") (pinfunction "2_2") (pintype "passive"))
      (node (ref "RP1") (pin "4") (pintype "passive"))
      (node (ref "RP1") (pin "5") (pintype "passive"))
      (node (ref "RP1") (pin "6") (pintype "passive"))
      (node (ref "RP5") (pin "12") (pintype "passive"))
      (node (ref "RP5") (pin "13") (pintype "passive"))
      (node (ref "RP5") (pin "14") (pintype "passive"))
      (node (ref "RP5") (pin "15") (pintype "passive"))
      (node (ref "RP5") (pin "16") (pintype "passive"))
      (node (ref "U10") (pin "20") (pinfunction "VCC_20") (pintype "power_in"))
      (node (ref "U11") (pin "20") (pinfunction "VCC_20") (pintype "power_in"))
      (node (ref "U2") (pin "20") (pinfunction "VCC_20") (pintype "power_in"))
      (node (ref "U27") (pin "20") (pinfunction "VCC_20") (pintype "power_in"))
      (node (ref "U3") (pin "12") (pinfunction "VCC_12") (pintype "power_in"))
      (node (ref "U3") (pin "34") (pinfunction "VCC_34") (pintype "power_in"))
      (node (ref "U4") (pin "20") (pinfunction "VCC_20") (pintype "power_in"))
      (node (ref "U7") (pin "4") (pinfunction "VCC_4") (pintype "power_in"))
      (node (ref "U8") (pin "20") (pinfunction "VCC_20") (pintype "power_in"))
      (node (ref "U9") (pin "43") (pinfunction "VCC_43") (pintype "power_in"))
      (node (ref "U9") (pin "9") (pinfunction "VCC_9") (pintype "power_in"))
      (node (ref "X1") (pin "4") (pinfunction "VCC_4") (pintype "power_in"))
    )
    (net (code "148") (name "unconnected-(RP1-Pad1)") (class "Default")
      (node (ref "RP1") (pin "1") (pintype "passive"))
    )
    (net (code "149") (name "unconnected-(RP1-Pad16)") (class "Default")
      (node (ref "RP1") (pin "16") (pintype "passive"))
    )
    (net (code "150") (name "unconnected-(RP5-Pad6)") (class "Default")
      (node (ref "RP5") (pin "6") (pintype "passive"))
    )
    (net (code "151") (name "unconnected-(RP5-Pad7)") (class "Default")
      (node (ref "RP5") (pin "7") (pintype "passive"))
    )
    (net (code "152") (name "unconnected-(RP5-Pad8)") (class "Default")
      (node (ref "RP5") (pin "8") (pintype "passive"))
    )
    (net (code "153") (name "unconnected-(RP5-Pad9)") (class "Default")
      (node (ref "RP5") (pin "9") (pintype "passive"))
    )
    (net (code "154") (name "unconnected-(RP5-Pad10)") (class "Default")
      (node (ref "RP5") (pin "10") (pintype "passive"))
    )
    (net (code "155") (name "unconnected-(RP5-Pad11)") (class "Default")
      (node (ref "RP5") (pin "11") (pintype "passive"))
    )
    (net (code "156") (name "unconnected-(U9-HLDA-Pad51)") (class "Default")
      (node (ref "U9") (pin "51") (pinfunction "HLDA_51") (pintype "output"))
    )
    (net (code "157") (name "unconnected-(U9-LOCK-Pad48)") (class "Default")
      (node (ref "U9") (pin "48") (pinfunction "LOCK_48") (pintype "tri_state"))
    )
    (net (code "158") (name "unconnected-(U9-RFSH-Pad64)") (class "Default")
      (node (ref "U9") (pin "64") (pinfunction "RFSH_64") (pintype "output"))
    )
    (net (code "159") (name "unconnected-(U9-S0-Pad52)") (class "Default")
      (node (ref "U9") (pin "52") (pinfunction "S0_52") (pintype "tri_state"))
    )
    (net (code "160") (name "unconnected-(U9-S1-Pad53)") (class "Default")
      (node (ref "U9") (pin "53") (pinfunction "S1_53") (pintype "tri_state"))
    )
    (net (code "161") (name "unconnected-(U9-S2-Pad54)") (class "Default")
      (node (ref "U9") (pin "54") (pinfunction "S2_54") (pintype "tri_state"))
    )
    (net (code "162") (name "unconnected-(U9-TMOUT0-Pad22)") (class "Default")
      (node (ref "U9") (pin "22") (pinfunction "TMOUT0_22") (pintype "output"))
    )
    (net (code "163") (name "unconnected-(U9-TMOUT1-Pad23)") (class "Default")
      (node (ref "U9") (pin "23") (pinfunction "TMOUT1_23") (pintype "output"))
    )
    (net (code "164") (name "unconnected-(U9-X2-Pad58)") (class "Default")
      (node (ref "U9") (pin "58") (pinfunction "X2_58") (pintype "input"))
    )
    (net (code "165") (name "unconnected-(U10-5Q-Pad15)") (class "Default")
      (node (ref "U10") (pin "15") (pinfunction "5Q_15") (pintype "output"))
    )
    (net (code "166") (name "unconnected-(U10-6Q-Pad14)") (class "Default")
      (node (ref "U10") (pin "14") (pinfunction "6Q_14") (pintype "output"))
    )
    (net (code "167") (name "unconnected-(U10-7Q-Pad13)") (class "Default")
      (node (ref "U10") (pin "13") (pinfunction "7Q_13") (pintype "output"))
    )
    (net (code "168") (name "unconnected-(U10-8Q-Pad12)") (class "Default")
      (node (ref "U10") (pin "12") (pinfunction "8Q_12") (pintype "output"))
    )
  )
)
